# SensorBoardR1a.net
KiCad netlist of a schematic drawn in EAGLE
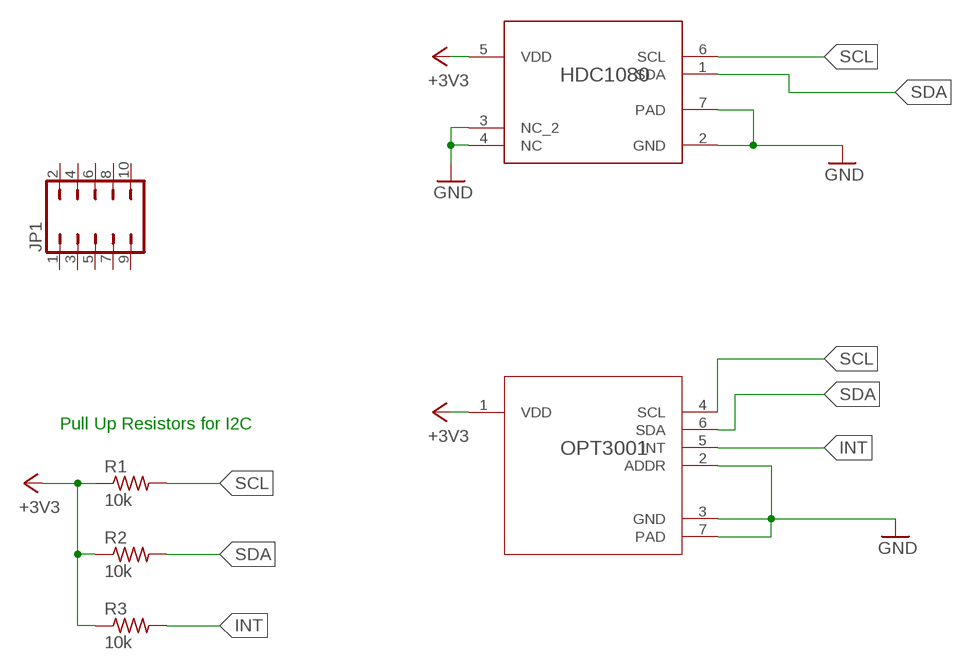
[diagram p0: schematic, sheet 1]

(export (version "E")
  (design (tool "Eeschema 10.0.6"))
  (components
    (comp (ref "HDC1080")
      (value "HDC1080DMBR")
      (footprint "eagle-import:DMB0006A")
      (fields
        (field (name "ALTERNATEPARTNUMBER") "HDC1080DMBT")
        (field (name "MANUFACTURER") "Texas Instruments")
      )
      (libsource (lib "eagle-import") (part "HDC1080DMBR"))
    )
    (comp (ref "JP1")
      (value "JP5Q")
      (footprint "eagle-import:JP5Q")
      (libsource (lib "eagle-import") (part "JP5Q"))
    )
    (comp (ref "OPT3001")
      (value "OPT3001DNPR")
      (footprint "eagle-import:DNP0006A")
      (fields (field (name "MANUFACTURER") "Texas Instruments") (field (name "PARTNUMBER") "OPT3001DNP"))
      (libsource (lib "eagle-import") (part "OPT3001DNPR"))
    )
    (comp (ref "R1")
      (value "10k")
      (footprint "eagle-import:R0805")
      (libsource (lib "eagle-import") (part "R-US_R0805"))
    )
    (comp (ref "R2")
      (value "10k")
      (footprint "eagle-import:R0805")
      (libsource (lib "eagle-import") (part "R-US_R0805"))
    )
    (comp (ref "R3")
      (value "10k")
      (footprint "eagle-import:R0805")
      (libsource (lib "eagle-import") (part "R-US_R0805"))
    )
  )
  (nets
    (net (code "1") (name "+3V3") (class "Default")
      (node (ref "HDC1080") (pin "5") (pinfunction "VDD_5") (pintype "power_in"))
      (node (ref "OPT3001") (pin "1") (pinfunction "VDD_1") (pintype "power_in"))
      (node (ref "R1") (pin "1") (pinfunction "1_1") (pintype "passive"))
      (node (ref "R2") (pin "1") (pinfunction "1_1") (pintype "passive"))
      (node (ref "R3") (pin "1") (pinfunction "1_1") (pintype "passive"))
    )
    (net (code "2") (name "GND") (class "Default")
      (node (ref "HDC1080") (pin "2") (pinfunction "GND_2") (pintype "power_in"))
      (node (ref "HDC1080") (pin "3") (pinfunction "NC_2_3") (pintype "passive"))
      (node (ref "HDC1080") (pin "4") (pinfunction "NC_4") (pintype "passive"))
      (node (ref "HDC1080") (pin "7") (pinfunction "PAD_7") (pintype "power_in"))
      (node (ref "OPT3001") (pin "2") (pinfunction "ADDR_2") (pintype "input"))
      (node (ref "OPT3001") (pin "3") (pinfunction "GND_3") (pintype "power_in"))
      (node (ref "OPT3001") (pin "7") (pinfunction "PAD_7") (pintype "passive"))
    )
    (net (code "3") (name "INT") (class "Default")
      (node (ref "OPT3001") (pin "5") (pinfunction "INT_5") (pintype "output"))
      (node (ref "R3") (pin "2") (pinfunction "2_2") (pintype "passive"))
    )
    (net (code "4") (name "SCL") (class "Default")
      (node (ref "HDC1080") (pin "6") (pinfunction "SCL_6") (pintype "open_collector"))
      (node (ref "OPT3001") (pin "4") (pinfunction "SCL_4") (pintype "input"))
      (node (ref "R1") (pin "2") (pinfunction "2_2") (pintype "passive"))
    )
    (net (code "5") (name "SDA") (class "Default")
      (node (ref "HDC1080") (pin "1") (pinfunction "SDA_1") (pintype "bidirectional"))
      (node (ref "OPT3001") (pin "6") (pinfunction "SDA_6") (pintype "input"))
      (node (ref "R2") (pin "2") (pinfunction "2_2") (pintype "passive"))
    )
    (net (code "6") (name "unconnected-(JP1-Pad1)") (class "Default")
      (node (ref "JP1") (pin "1") (pinfunction "1_1") (pintype "passive"))
    )
    (net (code "7") (name "unconnected-(JP1-Pad2)") (class "Default")
      (node (ref "JP1") (pin "2") (pinfunction "2_2") (pintype "passive"))
    )
    (net (code "8") (name "unconnected-(JP1-Pad3)") (class "Default")
      (node (ref "JP1") (pin "3") (pinfunction "3_3") (pintype "passive"))
    )
    (net (code "9") (name "unconnected-(JP1-Pad4)") (class "Default")
      (node (ref "JP1") (pin "4") (pinfunction "4_4") (pintype "passive"))
    )
    (net (code "10") (name "unconnected-(JP1-Pad5)") (class "Default")
      (node (ref "JP1") (pin "5") (pinfunction "5_5") (pintype "passive"))
    )
    (net (code "11") (name "unconnected-(JP1-Pad6)") (class "Default")
      (node (ref "JP1") (pin "6") (pinfunction "6_6") (pintype "passive"))
    )
    (net (code "12") (name "unconnected-(JP1-Pad7)") (class "Default")
      (node (ref "JP1") (pin "7") (pinfunction "7_7") (pintype "passive"))
    )
    (net (code "13") (name "unconnected-(JP1-Pad8)") (class "Default")
      (node (ref "JP1") (pin "8") (pinfunction "8_8") (pintype "passive"))
    )
    (net (code "14") (name "unconnected-(JP1-Pad9)") (class "Default")
      (node (ref "JP1") (pin "9") (pinfunction "9_9") (pintype "passive"))
    )
    (net (code "15") (name "unconnected-(JP1-Pad10)") (class "Default")
      (node (ref "JP1") (pin "10") (pinfunction "10_10") (pintype "passive"))
    )
  )
)
